# MegaButton_Shiled.net
KiCad netlist of a schematic drawn in EAGLE
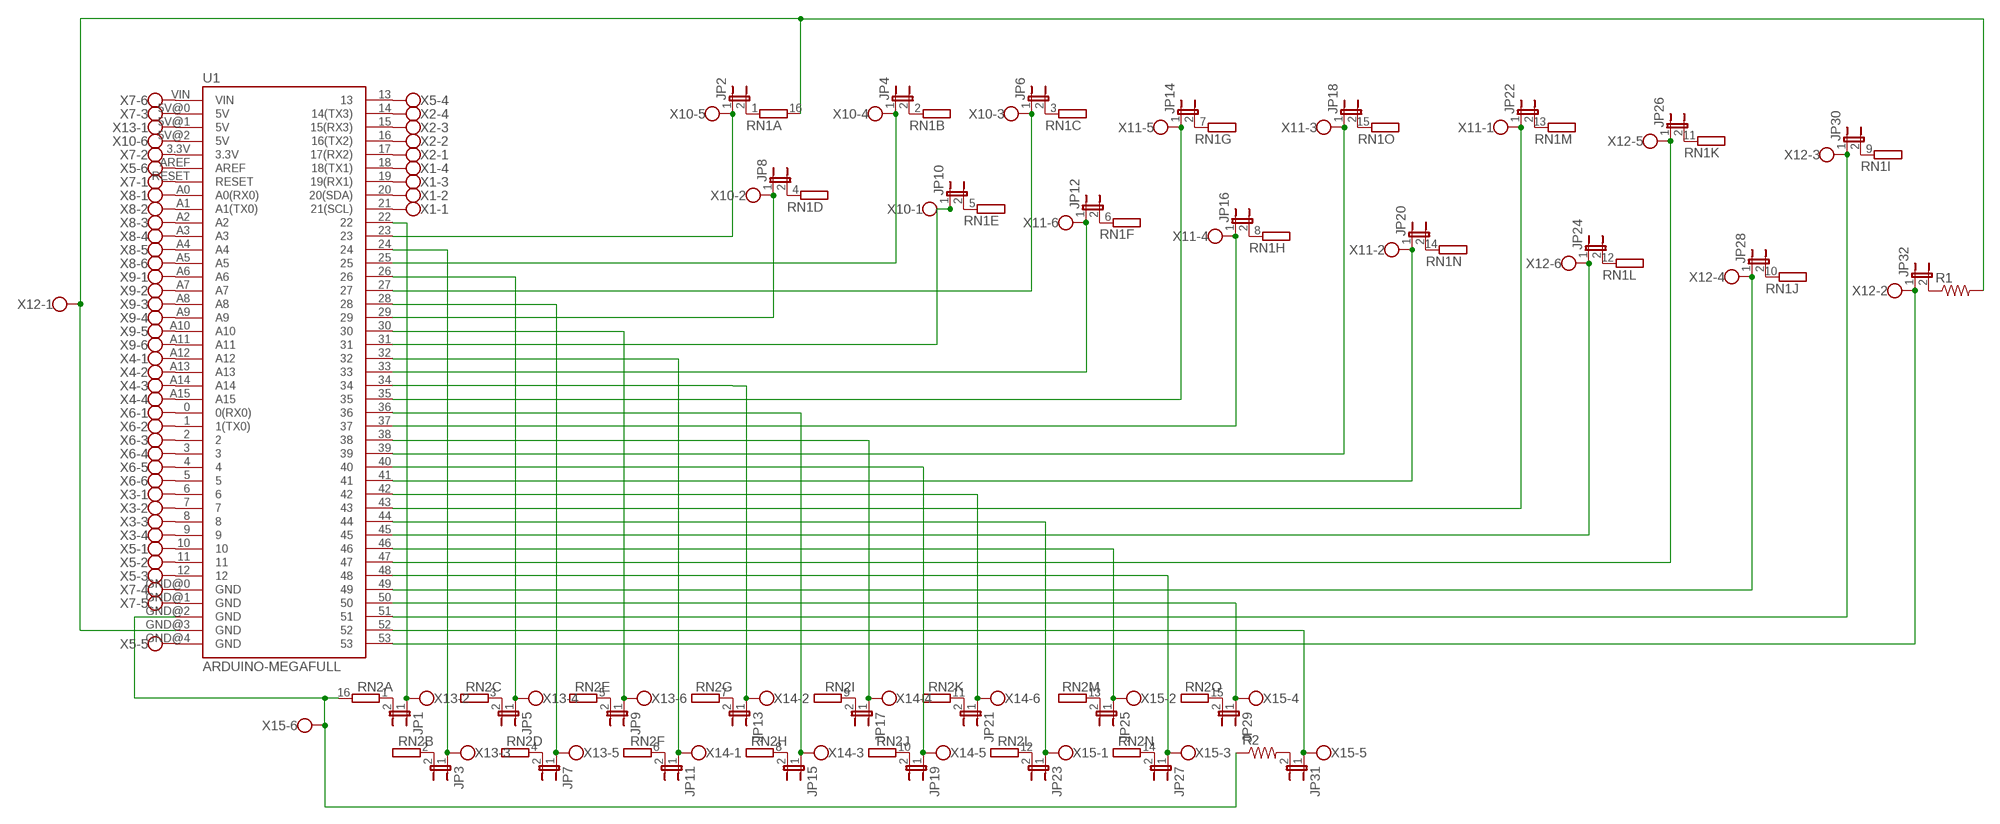
[diagram p0: schematic, sheet 1, part 1 of 2]
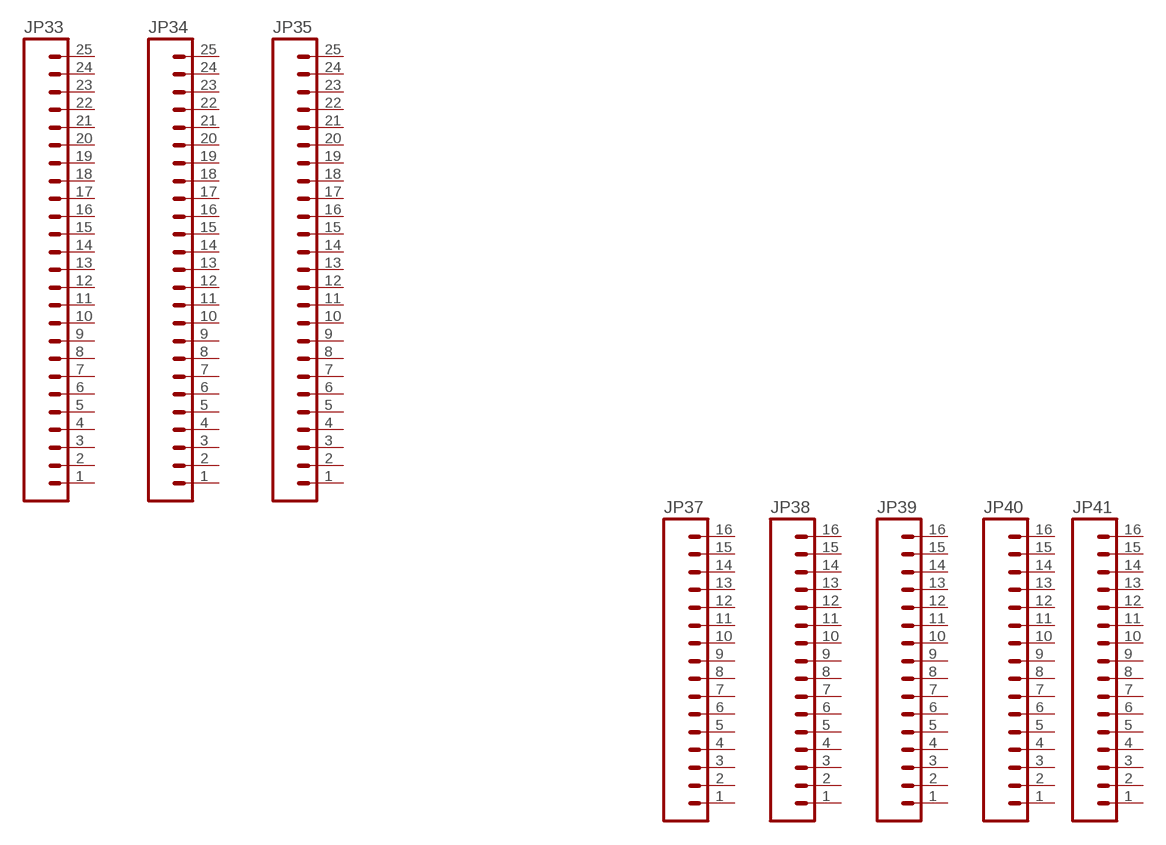
[diagram p1: schematic, sheet 1, part 2 of 2]

(export (version "E")
  (design (tool "Eeschema 10.0.6"))
  (components
    (comp (ref "JP1")
      (value "JP1E")
      (footprint "eagle-import:JP1")
      (libsource (lib "eagle-import") (part "JP1E"))
    )
    (comp (ref "JP2")
      (value "JP1E")
      (footprint "eagle-import:JP1")
      (libsource (lib "eagle-import") (part "JP1E"))
    )
    (comp (ref "JP3")
      (value "JP1E")
      (footprint "eagle-import:JP1")
      (libsource (lib "eagle-import") (part "JP1E"))
    )
    (comp (ref "JP4")
      (value "JP1E")
      (footprint "eagle-import:JP1")
      (libsource (lib "eagle-import") (part "JP1E"))
    )
    (comp (ref "JP5")
      (value "JP1E")
      (footprint "eagle-import:JP1")
      (libsource (lib "eagle-import") (part "JP1E"))
    )
    (comp (ref "JP6")
      (value "JP1E")
      (footprint "eagle-import:JP1")
      (libsource (lib "eagle-import") (part "JP1E"))
    )
    (comp (ref "JP7")
      (value "JP1E")
      (footprint "eagle-import:JP1")
      (libsource (lib "eagle-import") (part "JP1E"))
    )
    (comp (ref "JP8")
      (value "JP1E")
      (footprint "eagle-import:JP1")
      (libsource (lib "eagle-import") (part "JP1E"))
    )
    (comp (ref "JP9")
      (value "JP1E")
      (footprint "eagle-import:JP1")
      (libsource (lib "eagle-import") (part "JP1E"))
    )
    (comp (ref "JP10")
      (value "JP1E")
      (footprint "eagle-import:JP1")
      (libsource (lib "eagle-import") (part "JP1E"))
    )
    (comp (ref "JP11")
      (value "JP1E")
      (footprint "eagle-import:JP1")
      (libsource (lib "eagle-import") (part "JP1E"))
    )
    (comp (ref "JP12")
      (value "JP1E")
      (footprint "eagle-import:JP1")
      (libsource (lib "eagle-import") (part "JP1E"))
    )
    (comp (ref "JP13")
      (value "JP1E")
      (footprint "eagle-import:JP1")
      (libsource (lib "eagle-import") (part "JP1E"))
    )
    (comp (ref "JP14")
      (value "JP1E")
      (footprint "eagle-import:JP1")
      (libsource (lib "eagle-import") (part "JP1E"))
    )
    (comp (ref "JP15")
      (value "JP1E")
      (footprint "eagle-import:JP1")
      (libsource (lib "eagle-import") (part "JP1E"))
    )
    (comp (ref "JP16")
      (value "JP1E")
      (footprint "eagle-import:JP1")
      (libsource (lib "eagle-import") (part "JP1E"))
    )
    (comp (ref "JP17")
      (value "JP1E")
      (footprint "eagle-import:JP1")
      (libsource (lib "eagle-import") (part "JP1E"))
    )
    (comp (ref "JP18")
      (value "JP1E")
      (footprint "eagle-import:JP1")
      (libsource (lib "eagle-import") (part "JP1E"))
    )
    (comp (ref "JP19")
      (value "JP1E")
      (footprint "eagle-import:JP1")
      (libsource (lib "eagle-import") (part "JP1E"))
    )
    (comp (ref "JP20")
      (value "JP1E")
      (footprint "eagle-import:JP1")
      (libsource (lib "eagle-import") (part "JP1E"))
    )
    (comp (ref "JP21")
      (value "JP1E")
      (footprint "eagle-import:JP1")
      (libsource (lib "eagle-import") (part "JP1E"))
    )
    (comp (ref "JP22")
      (value "JP1E")
      (footprint "eagle-import:JP1")
      (libsource (lib "eagle-import") (part "JP1E"))
    )
    (comp (ref "JP23")
      (value "JP1E")
      (footprint "eagle-import:JP1")
      (libsource (lib "eagle-import") (part "JP1E"))
    )
    (comp (ref "JP24")
      (value "JP1E")
      (footprint "eagle-import:JP1")
      (libsource (lib "eagle-import") (part "JP1E"))
    )
    (comp (ref "JP25")
      (value "JP1E")
      (footprint "eagle-import:JP1")
      (libsource (lib "eagle-import") (part "JP1E"))
    )
    (comp (ref "JP26")
      (value "JP1E")
      (footprint "eagle-import:JP1")
      (libsource (lib "eagle-import") (part "JP1E"))
    )
    (comp (ref "JP27")
      (value "JP1E")
      (footprint "eagle-import:JP1")
      (libsource (lib "eagle-import") (part "JP1E"))
    )
    (comp (ref "JP28")
      (value "JP1E")
      (footprint "eagle-import:JP1")
      (libsource (lib "eagle-import") (part "JP1E"))
    )
    (comp (ref "JP29")
      (value "JP1E")
      (footprint "eagle-import:JP1")
      (libsource (lib "eagle-import") (part "JP1E"))
    )
    (comp (ref "JP30")
      (value "JP1E")
      (footprint "eagle-import:JP1")
      (libsource (lib "eagle-import") (part "JP1E"))
    )
    (comp (ref "JP31")
      (value "JP1E")
      (footprint "eagle-import:JP1")
      (libsource (lib "eagle-import") (part "JP1E"))
    )
    (comp (ref "JP32")
      (value "JP1E")
      (footprint "eagle-import:JP1")
      (libsource (lib "eagle-import") (part "JP1E"))
    )
    (comp (ref "JP33")
      (value "M25PTH")
      (footprint "eagle-import:1X25")
      (libsource (lib "eagle-import") (part "M25PTH"))
    )
    (comp (ref "JP34")
      (value "M25PTH")
      (footprint "eagle-import:1X25")
      (libsource (lib "eagle-import") (part "M25PTH"))
    )
    (comp (ref "JP35")
      (value "M25PTH")
      (footprint "eagle-import:1X25")
      (libsource (lib "eagle-import") (part "M25PTH"))
    )
    (comp (ref "JP37")
      (value "M16PTH")
      (footprint "eagle-import:1X16")
      (libsource (lib "eagle-import") (part "M16PTH"))
    )
    (comp (ref "JP38")
      (value "M16PTH")
      (footprint "eagle-import:1X16")
      (libsource (lib "eagle-import") (part "M16PTH"))
    )
    (comp (ref "JP39")
      (value "M16PTH")
      (footprint "eagle-import:1X16")
      (libsource (lib "eagle-import") (part "M16PTH"))
    )
    (comp (ref "JP40")
      (value "M16PTH")
      (footprint "eagle-import:1X16")
      (libsource (lib "eagle-import") (part "M16PTH"))
    )
    (comp (ref "JP41")
      (value "M16PTH")
      (footprint "eagle-import:1X16")
      (libsource (lib "eagle-import") (part "M16PTH"))
    )
    (comp (ref "R1")
      (value "R-US_0204/5")
      (footprint "eagle-import:0204_5")
      (libsource (lib "eagle-import") (part "R-US_0204/5"))
    )
    (comp (ref "R2")
      (value "R-US_0204/5")
      (footprint "eagle-import:0204_5")
      (libsource (lib "eagle-import") (part "R-US_0204/5"))
    )
    (comp (ref "RN1")
      (value "E15R")
      (footprint "eagle-import:DIL16")
      (libsource (lib "eagle-import") (part "E15R"))
    )
    (comp (ref "RN2")
      (value "E15R")
      (footprint "eagle-import:DIL16")
      (libsource (lib "eagle-import") (part "E15R"))
    )
    (comp (ref "U1")
      (value "ARDUINO-MEGAFULL")
      (footprint "eagle-import:ARDUINO_MEGA")
      (libsource (lib "eagle-import") (part "ARDUINO-MEGAFULL"))
    )
    (comp (ref "X1")
      (value "W237-4")
      (footprint "eagle-import:W237-4")
      (libsource (lib "eagle-import") (part "W237-4"))
    )
    (comp (ref "X2")
      (value "W237-4")
      (footprint "eagle-import:W237-4")
      (libsource (lib "eagle-import") (part "W237-4"))
    )
    (comp (ref "X3")
      (value "W237-4")
      (footprint "eagle-import:W237-4")
      (libsource (lib "eagle-import") (part "W237-4"))
    )
    (comp (ref "X4")
      (value "W237-4")
      (footprint "eagle-import:W237-4")
      (libsource (lib "eagle-import") (part "W237-4"))
    )
    (comp (ref "X5")
      (value "W237-136")
      (footprint "eagle-import:W237-136")
      (fields (field (name "MPN") "237-136"))
      (libsource (lib "eagle-import") (part "W237-136"))
    )
    (comp (ref "X6")
      (value "W237-136")
      (footprint "eagle-import:W237-136")
      (fields (field (name "MPN") "237-136"))
      (libsource (lib "eagle-import") (part "W237-136"))
    )
    (comp (ref "X7")
      (value "W237-136")
      (footprint "eagle-import:W237-136")
      (fields (field (name "MPN") "237-136"))
      (libsource (lib "eagle-import") (part "W237-136"))
    )
    (comp (ref "X8")
      (value "W237-6")
      (footprint "eagle-import:W237-6")
      (libsource (lib "eagle-import") (part "W237-6"))
    )
    (comp (ref "X9")
      (value "W237-6")
      (footprint "eagle-import:W237-6")
      (libsource (lib "eagle-import") (part "W237-6"))
    )
    (comp (ref "X10")
      (value "W237-6")
      (footprint "eagle-import:W237-6")
      (libsource (lib "eagle-import") (part "W237-6"))
    )
    (comp (ref "X11")
      (value "W237-6")
      (footprint "eagle-import:W237-6")
      (libsource (lib "eagle-import") (part "W237-6"))
    )
    (comp (ref "X12")
      (value "W237-6")
      (footprint "eagle-import:W237-6")
      (libsource (lib "eagle-import") (part "W237-6"))
    )
    (comp (ref "X13")
      (value "W237-6")
      (footprint "eagle-import:W237-6")
      (libsource (lib "eagle-import") (part "W237-6"))
    )
    (comp (ref "X14")
      (value "W237-6")
      (footprint "eagle-import:W237-6")
      (libsource (lib "eagle-import") (part "W237-6"))
    )
    (comp (ref "X15")
      (value "W237-6")
      (footprint "eagle-import:W237-6")
      (libsource (lib "eagle-import") (part "W237-6"))
    )
  )
  (nets
    (net (code "1") (name "Net-(JP1-Pad2)") (class "Default")
      (node (ref "JP1") (pin "2") (pinfunction "2_2") (pintype "passive"))
      (node (ref "RN2") (pin "1") (pinfunction "1_1") (pintype "passive"))
    )
    (net (code "2") (name "Net-(JP2-Pad2)") (class "Default")
      (node (ref "JP2") (pin "2") (pinfunction "2_2") (pintype "passive"))
      (node (ref "RN1") (pin "1") (pinfunction "1_1") (pintype "passive"))
    )
    (net (code "3") (name "Net-(JP31-Pad2)") (class "Default")
      (node (ref "JP31") (pin "2") (pinfunction "2_2") (pintype "passive"))
      (node (ref "R2") (pin "2") (pinfunction "2_2") (pintype "passive"))
    )
    (net (code "4") (name "Net-(JP32-Pad2)") (class "Default")
      (node (ref "JP32") (pin "2") (pinfunction "2_2") (pintype "passive"))
      (node (ref "R1") (pin "1") (pinfunction "1_1") (pintype "passive"))
    )
    (net (code "5") (name "Net-(RN1A-2)") (class "Default")
      (node (ref "R1") (pin "2") (pinfunction "2_2") (pintype "passive"))
      (node (ref "RN1") (pin "16") (pinfunction "2_16") (pintype "passive"))
      (node (ref "U1") (pin "GND@3") (pinfunction "GND_GND@3") (pintype "bidirectional"))
      (node (ref "X12") (pin "1") (pinfunction "KL_1") (pintype "passive"))
    )
    (net (code "6") (name "Net-(RN1B-1)") (class "Default")
      (node (ref "JP4") (pin "2") (pinfunction "2_2") (pintype "passive"))
      (node (ref "RN1") (pin "2") (pinfunction "1_2") (pintype "passive"))
    )
    (net (code "7") (name "Net-(RN1C-1)") (class "Default")
      (node (ref "JP6") (pin "2") (pinfunction "2_2") (pintype "passive"))
      (node (ref "RN1") (pin "3") (pinfunction "1_3") (pintype "passive"))
    )
    (net (code "8") (name "Net-(RN1D-1)") (class "Default")
      (node (ref "JP8") (pin "2") (pinfunction "2_2") (pintype "passive"))
      (node (ref "RN1") (pin "4") (pinfunction "1_4") (pintype "passive"))
    )
    (net (code "9") (name "Net-(RN1E-1)") (class "Default")
      (node (ref "JP10") (pin "2") (pinfunction "2_2") (pintype "passive"))
      (node (ref "RN1") (pin "5") (pinfunction "1_5") (pintype "passive"))
    )
    (net (code "10") (name "Net-(RN1F-1)") (class "Default")
      (node (ref "JP12") (pin "2") (pinfunction "2_2") (pintype "passive"))
      (node (ref "RN1") (pin "6") (pinfunction "1_6") (pintype "passive"))
    )
    (net (code "11") (name "Net-(RN1G-1)") (class "Default")
      (node (ref "JP14") (pin "2") (pinfunction "2_2") (pintype "passive"))
      (node (ref "RN1") (pin "7") (pinfunction "1_7") (pintype "passive"))
    )
    (net (code "12") (name "Net-(RN1H-1)") (class "Default")
      (node (ref "JP16") (pin "2") (pinfunction "2_2") (pintype "passive"))
      (node (ref "RN1") (pin "8") (pinfunction "1_8") (pintype "passive"))
    )
    (net (code "13") (name "Net-(RN1I-1)") (class "Default")
      (node (ref "JP30") (pin "2") (pinfunction "2_2") (pintype "passive"))
      (node (ref "RN1") (pin "9") (pinfunction "1_9") (pintype "passive"))
    )
    (net (code "14") (name "Net-(RN1J-1)") (class "Default")
      (node (ref "JP28") (pin "2") (pinfunction "2_2") (pintype "passive"))
      (node (ref "RN1") (pin "10") (pinfunction "1_10") (pintype "passive"))
    )
    (net (code "15") (name "Net-(RN1K-1)") (class "Default")
      (node (ref "JP26") (pin "2") (pinfunction "2_2") (pintype "passive"))
      (node (ref "RN1") (pin "11") (pinfunction "1_11") (pintype "passive"))
    )
    (net (code "16") (name "Net-(RN1L-1)") (class "Default")
      (node (ref "JP24") (pin "2") (pinfunction "2_2") (pintype "passive"))
      (node (ref "RN1") (pin "12") (pinfunction "1_12") (pintype "passive"))
    )
    (net (code "17") (name "Net-(RN1M-1)") (class "Default")
      (node (ref "JP22") (pin "2") (pinfunction "2_2") (pintype "passive"))
      (node (ref "RN1") (pin "13") (pinfunction "1_13") (pintype "passive"))
    )
    (net (code "18") (name "Net-(RN1N-1)") (class "Default")
      (node (ref "JP20") (pin "2") (pinfunction "2_2") (pintype "passive"))
      (node (ref "RN1") (pin "14") (pinfunction "1_14") (pintype "passive"))
    )
    (net (code "19") (name "Net-(RN1O-1)") (class "Default")
      (node (ref "JP18") (pin "2") (pinfunction "2_2") (pintype "passive"))
      (node (ref "RN1") (pin "15") (pinfunction "1_15") (pintype "passive"))
    )
    (net (code "20") (name "Net-(RN2A-2)") (class "Default")
      (node (ref "R2") (pin "1") (pinfunction "1_1") (pintype "passive"))
      (node (ref "RN2") (pin "16") (pinfunction "2_16") (pintype "passive"))
      (node (ref "U1") (pin "GND@2") (pinfunction "GND_GND@2") (pintype "bidirectional"))
      (node (ref "X15") (pin "6") (pinfunction "KL_6") (pintype "passive"))
    )
    (net (code "21") (name "Net-(RN2B-1)") (class "Default")
      (node (ref "JP3") (pin "2") (pinfunction "2_2") (pintype "passive"))
      (node (ref "RN2") (pin "2") (pinfunction "1_2") (pintype "passive"))
    )
    (net (code "22") (name "Net-(RN2C-1)") (class "Default")
      (node (ref "JP5") (pin "2") (pinfunction "2_2") (pintype "passive"))
      (node (ref "RN2") (pin "3") (pinfunction "1_3") (pintype "passive"))
    )
    (net (code "23") (name "Net-(RN2D-1)") (class "Default")
      (node (ref "JP7") (pin "2") (pinfunction "2_2") (pintype "passive"))
      (node (ref "RN2") (pin "4") (pinfunction "1_4") (pintype "passive"))
    )
    (net (code "24") (name "Net-(RN2E-1)") (class "Default")
      (node (ref "JP9") (pin "2") (pinfunction "2_2") (pintype "passive"))
      (node (ref "RN2") (pin "5") (pinfunction "1_5") (pintype "passive"))
    )
    (net (code "25") (name "Net-(RN2F-1)") (class "Default")
      (node (ref "JP11") (pin "2") (pinfunction "2_2") (pintype "passive"))
      (node (ref "RN2") (pin "6") (pinfunction "1_6") (pintype "passive"))
    )
    (net (code "26") (name "Net-(RN2G-1)") (class "Default")
      (node (ref "JP13") (pin "2") (pinfunction "2_2") (pintype "passive"))
      (node (ref "RN2") (pin "7") (pinfunction "1_7") (pintype "passive"))
    )
    (net (code "27") (name "Net-(RN2H-1)") (class "Default")
      (node (ref "JP15") (pin "2") (pinfunction "2_2") (pintype "passive"))
      (node (ref "RN2") (pin "8") (pinfunction "1_8") (pintype "passive"))
    )
    (net (code "28") (name "Net-(RN2I-1)") (class "Default")
      (node (ref "JP17") (pin "2") (pinfunction "2_2") (pintype "passive"))
      (node (ref "RN2") (pin "9") (pinfunction "1_9") (pintype "passive"))
    )
    (net (code "29") (name "Net-(RN2J-1)") (class "Default")
      (node (ref "JP19") (pin "2") (pinfunction "2_2") (pintype "passive"))
      (node (ref "RN2") (pin "10") (pinfunction "1_10") (pintype "passive"))
    )
    (net (code "30") (name "Net-(RN2K-1)") (class "Default")
      (node (ref "JP21") (pin "2") (pinfunction "2_2") (pintype "passive"))
      (node (ref "RN2") (pin "11") (pinfunction "1_11") (pintype "passive"))
    )
    (net (code "31") (name "Net-(RN2L-1)") (class "Default")
      (node (ref "JP23") (pin "2") (pinfunction "2_2") (pintype "passive"))
      (node (ref "RN2") (pin "12") (pinfunction "1_12") (pintype "passive"))
    )
    (net (code "32") (name "Net-(RN2M-1)") (class "Default")
      (node (ref "JP25") (pin "2") (pinfunction "2_2") (pintype "passive"))
      (node (ref "RN2") (pin "13") (pinfunction "1_13") (pintype "passive"))
    )
    (net (code "33") (name "Net-(RN2N-1)") (class "Default")
      (node (ref "JP27") (pin "2") (pinfunction "2_2") (pintype "passive"))
      (node (ref "RN2") (pin "14") (pinfunction "1_14") (pintype "passive"))
    )
    (net (code "34") (name "Net-(RN2O-1)") (class "Default")
      (node (ref "JP29") (pin "2") (pinfunction "2_2") (pintype "passive"))
      (node (ref "RN2") (pin "15") (pinfunction "1_15") (pintype "passive"))
    )
    (net (code "35") (name "Net-(U1-0(RX0))") (class "Default")
      (node (ref "U1") (pin "0") (pinfunction "0(RX0)_0") (pintype "bidirectional"))
      (node (ref "X6") (pin "1") (pinfunction "KL_1") (pintype "passive"))
    )
    (net (code "36") (name "Net-(U1-1(TX0))") (class "Default")
      (node (ref "U1") (pin "1") (pinfunction "1(TX0)_1") (pintype "bidirectional"))
      (node (ref "X6") (pin "2") (pinfunction "KL_2") (pintype "passive"))
    )
    (net (code "37") (name "Net-(U1-14(TX3))") (class "Default")
      (node (ref "U1") (pin "14") (pinfunction "14(TX3)_14") (pintype "bidirectional"))
      (node (ref "X2") (pin "4") (pinfunction "KL_4") (pintype "passive"))
    )
    (net (code "38") (name "Net-(U1-15(RX3))") (class "Default")
      (node (ref "U1") (pin "15") (pinfunction "15(RX3)_15") (pintype "bidirectional"))
      (node (ref "X2") (pin "3") (pinfunction "KL_3") (pintype "passive"))
    )
    (net (code "39") (name "Net-(U1-16(TX2))") (class "Default")
      (node (ref "U1") (pin "16") (pinfunction "16(TX2)_16") (pintype "bidirectional"))
      (node (ref "X2") (pin "2") (pinfunction "KL_2") (pintype "passive"))
    )
    (net (code "40") (name "Net-(U1-17(RX2))") (class "Default")
      (node (ref "U1") (pin "17") (pinfunction "17(RX2)_17") (pintype "bidirectional"))
      (node (ref "X2") (pin "1") (pinfunction "KL_1") (pintype "passive"))
    )
    (net (code "41") (name "Net-(U1-18(TX1))") (class "Default")
      (node (ref "U1") (pin "18") (pinfunction "18(TX1)_18") (pintype "bidirectional"))
      (node (ref "X1") (pin "4") (pinfunction "KL_4") (pintype "passive"))
    )
    (net (code "42") (name "Net-(U1-19(RX1))") (class "Default")
      (node (ref "U1") (pin "19") (pinfunction "19(RX1)_19") (pintype "bidirectional"))
      (node (ref "X1") (pin "3") (pinfunction "KL_3") (pintype "passive"))
    )
    (net (code "43") (name "Net-(U1-20(SDA))") (class "Default")
      (node (ref "U1") (pin "20") (pinfunction "20(SDA)_20") (pintype "bidirectional"))
      (node (ref "X1") (pin "2") (pinfunction "KL_2") (pintype "passive"))
    )
    (net (code "44") (name "Net-(U1-21(SCL))") (class "Default")
      (node (ref "U1") (pin "21") (pinfunction "21(SCL)_21") (pintype "bidirectional"))
      (node (ref "X1") (pin "1") (pinfunction "KL_1") (pintype "passive"))
    )
    (net (code "45") (name "Net-(U1-A0(RX0))") (class "Default")
      (node (ref "U1") (pin "A0") (pinfunction "A0(RX0)_A0") (pintype "bidirectional"))
      (node (ref "X8") (pin "1") (pinfunction "KL_1") (pintype "passive"))
    )
    (net (code "46") (name "Net-(U1-A1(TX0))") (class "Default")
      (node (ref "U1") (pin "A1") (pinfunction "A1(TX0)_A1") (pintype "bidirectional"))
      (node (ref "X8") (pin "2") (pinfunction "KL_2") (pintype "passive"))
    )
    (net (code "47") (name "Net-(X3A-KL)") (class "Default")
      (node (ref "U1") (pin "6") (pinfunction "6_6") (pintype "bidirectional"))
      (node (ref "X3") (pin "1") (pinfunction "KL_1") (pintype "passive"))
    )
    (net (code "48") (name "Net-(X3B-KL)") (class "Default")
      (node (ref "U1") (pin "7") (pinfunction "7_7") (pintype "bidirectional"))
      (node (ref "X3") (pin "2") (pinfunction "KL_2") (pintype "passive"))
    )
    (net (code "49") (name "Net-(X3C-KL)") (class "Default")
      (node (ref "U1") (pin "8") (pinfunction "8_8") (pintype "bidirectional"))
      (node (ref "X3") (pin "3") (pinfunction "KL_3") (pintype "passive"))
    )
    (net (code "50") (name "Net-(X3D-KL)") (class "Default")
      (node (ref "U1") (pin "9") (pinfunction "9_9") (pintype "bidirectional"))
      (node (ref "X3") (pin "4") (pinfunction "KL_4") (pintype "passive"))
    )
    (net (code "51") (name "Net-(X4A-KL)") (class "Default")
      (node (ref "U1") (pin "A12") (pinfunction "A12_A12") (pintype "bidirectional"))
      (node (ref "X4") (pin "1") (pinfunction "KL_1") (pintype "passive"))
    )
    (net (code "52") (name "Net-(X4B-KL)") (class "Default")
      (node (ref "U1") (pin "A13") (pinfunction "A13_A13") (pintype "bidirectional"))
      (node (ref "X4") (pin "2") (pinfunction "KL_2") (pintype "passive"))
    )
    (net (code "53") (name "Net-(X4C-KL)") (class "Default")
      (node (ref "U1") (pin "A14") (pinfunction "A14_A14") (pintype "bidirectional"))
      (node (ref "X4") (pin "3") (pinfunction "KL_3") (pintype "passive"))
    )
    (net (code "54") (name "Net-(X4D-KL)") (class "Default")
      (node (ref "U1") (pin "A15") (pinfunction "A15_A15") (pintype "bidirectional"))
      (node (ref "X4") (pin "4") (pinfunction "KL_4") (pintype "passive"))
    )
    (net (code "55") (name "Net-(X5A-KL)") (class "Default")
      (node (ref "U1") (pin "10") (pinfunction "10_10") (pintype "bidirectional"))
      (node (ref "X5") (pin "1") (pinfunction "KL_1") (pintype "passive"))
    )
    (net (code "56") (name "Net-(X5B-KL)") (class "Default")
      (node (ref "U1") (pin "11") (pinfunction "11_11") (pintype "bidirectional"))
      (node (ref "X5") (pin "2") (pinfunction "KL_2") (pintype "passive"))
    )
    (net (code "57") (name "Net-(X5C-KL)") (class "Default")
      (node (ref "U1") (pin "12") (pinfunction "12_12") (pintype "bidirectional"))
      (node (ref "X5") (pin "3") (pinfunction "KL_3") (pintype "passive"))
    )
    (net (code "58") (name "Net-(X5D-KL)") (class "Default")
      (node (ref "U1") (pin "13") (pinfunction "13_13") (pintype "bidirectional"))
      (node (ref "X5") (pin "4") (pinfunction "KL_4") (pintype "passive"))
    )
    (net (code "59") (name "Net-(X5E-KL)") (class "Default")
      (node (ref "U1") (pin "GND@4") (pinfunction "GND_GND@4") (pintype "bidirectional"))
      (node (ref "X5") (pin "5") (pinfunction "KL_5") (pintype "passive"))
    )
    (net (code "60") (name "Net-(X5F-KL)") (class "Default")
      (node (ref "U1") (pin "AREF") (pinfunction "AREF_AREF") (pintype "bidirectional"))
      (node (ref "X5") (pin "6") (pinfunction "KL_6") (pintype "passive"))
    )
    (net (code "61") (name "Net-(X6C-KL)") (class "Default")
      (node (ref "U1") (pin "2") (pinfunction "2_2") (pintype "bidirectional"))
      (node (ref "X6") (pin "3") (pinfunction "KL_3") (pintype "passive"))
    )
    (net (code "62") (name "Net-(X6D-KL)") (class "Default")
      (node (ref "U1") (pin "3") (pinfunction "3_3") (pintype "bidirectional"))
      (node (ref "X6") (pin "4") (pinfunction "KL_4") (pintype "passive"))
    )
    (net (code "63") (name "Net-(X6E-KL)") (class "Default")
      (node (ref "U1") (pin "4") (pinfunction "4_4") (pintype "bidirectional"))
      (node (ref "X6") (pin "5") (pinfunction "KL_5") (pintype "passive"))
    )
    (net (code "64") (name "Net-(X6F-KL)") (class "Default")
      (node (ref "U1") (pin "5") (pinfunction "5_5") (pintype "bidirectional"))
      (node (ref "X6") (pin "6") (pinfunction "KL_6") (pintype "passive"))
    )
    (net (code "65") (name "Net-(X7A-KL)") (class "Default")
      (node (ref "U1") (pin "RESET") (pinfunction "RESET_RESET") (pintype "bidirectional"))
      (node (ref "X7") (pin "1") (pinfunction "KL_1") (pintype "passive"))
    )
    (net (code "66") (name "Net-(X7B-KL)") (class "Default")
      (node (ref "U1") (pin "3.3V") (pinfunction "3.3V_3.3V") (pintype "bidirectional"))
      (node (ref "X7") (pin "2") (pinfunction "KL_2") (pintype "passive"))
    )
    (net (code "67") (name "Net-(X7C-KL)") (class "Default")
      (node (ref "U1") (pin "5V@0") (pinfunction "5V_5V@0") (pintype "bidirectional"))
      (node (ref "X7") (pin "3") (pinfunction "KL_3") (pintype "passive"))
    )
    (net (code "68") (name "Net-(X7D-KL)") (class "Default")
      (node (ref "U1") (pin "GND@0") (pinfunction "GND_GND@0") (pintype "bidirectional"))
      (node (ref "X7") (pin "4") (pinfunction "KL_4") (pintype "passive"))
    )
    (net (code "69") (name "Net-(X7E-KL)") (class "Default")
      (node (ref "U1") (pin "GND@1") (pinfunction "GND_GND@1") (pintype "bidirectional"))
      (node (ref "X7") (pin "5") (pinfunction "KL_5") (pintype "passive"))
    )
    (net (code "70") (name "Net-(X7F-KL)") (class "Default")
      (node (ref "U1") (pin "VIN") (pinfunction "VIN_VIN") (pintype "bidirectional"))
      (node (ref "X7") (pin "6") (pinfunction "KL_6") (pintype "passive"))
    )
    (net (code "71") (name "Net-(X8C-KL)") (class "Default")
      (node (ref "U1") (pin "A2") (pinfunction "A2_A2") (pintype "bidirectional"))
      (node (ref "X8") (pin "3") (pinfunction "KL_3") (pintype "passive"))
    )
    (net (code "72") (name "Net-(X8D-KL)") (class "Default")
      (node (ref "U1") (pin "A3") (pinfunction "A3_A3") (pintype "bidirectional"))
      (node (ref "X8") (pin "4") (pinfunction "KL_4") (pintype "passive"))
    )
    (net (code "73") (name "Net-(X8E-KL)") (class "Default")
      (node (ref "U1") (pin "A4") (pinfunction "A4_A4") (pintype "bidirectional"))
      (node (ref "X8") (pin "5") (pinfunction "KL_5") (pintype "passive"))
    )
    (net (code "74") (name "Net-(X8F-KL)") (class "Default")
      (node (ref "U1") (pin "A5") (pinfunction "A5_A5") (pintype "bidirectional"))
      (node (ref "X8") (pin "6") (pinfunction "KL_6") (pintype "passive"))
    )
    (net (code "75") (name "Net-(X9A-KL)") (class "Default")
      (node (ref "U1") (pin "A6") (pinfunction "A6_A6") (pintype "bidirectional"))
      (node (ref "X9") (pin "1") (pinfunction "KL_1") (pintype "passive"))
    )
    (net (code "76") (name "Net-(X9B-KL)") (class "Default")
      (node (ref "U1") (pin "A7") (pinfunction "A7_A7") (pintype "bidirectional"))
      (node (ref "X9") (pin "2") (pinfunction "KL_2") (pintype "passive"))
    )
    (net (code "77") (name "Net-(X9C-KL)") (class "Default")
      (node (ref "U1") (pin "A8") (pinfunction "A8_A8") (pintype "bidirectional"))
      (node (ref "X9") (pin "3") (pinfunction "KL_3") (pintype "passive"))
    )
    (net (code "78") (name "Net-(X9D-KL)") (class "Default")
      (node (ref "U1") (pin "A9") (pinfunction "A9_A9") (pintype "bidirectional"))
      (node (ref "X9") (pin "4") (pinfunction "KL_4") (pintype "passive"))
    )
    (net (code "79") (name "Net-(X9E-KL)") (class "Default")
      (node (ref "U1") (pin "A10") (pinfunction "A10_A10") (pintype "bidirectional"))
      (node (ref "X9") (pin "5") (pinfunction "KL_5") (pintype "passive"))
    )
    (net (code "80") (name "Net-(X9F-KL)") (class "Default")
      (node (ref "U1") (pin "A11") (pinfunction "A11_A11") (pintype "bidirectional"))
      (node (ref "X9") (pin "6") (pinfunction "KL_6") (pintype "passive"))
    )
    (net (code "81") (name "Net-(X10A-KL)") (class "Default")
      (node (ref "JP10") (pin "1") (pinfunction "1_1") (pintype "passive"))
      (node (ref "U1") (pin "31") (pinfunction "31_31") (pintype "bidirectional"))
      (node (ref "X10") (pin "1") (pinfunction "KL_1") (pintype "passive"))
    )
    (net (code "82") (name "Net-(X10B-KL)") (class "Default")
      (node (ref "JP8") (pin "1") (pinfunction "1_1") (pintype "passive"))
      (node (ref "U1") (pin "29") (pinfunction "29_29") (pintype "bidirectional"))
      (node (ref "X10") (pin "2") (pinfunction "KL_2") (pintype "passive"))
    )
    (net (code "83") (name "Net-(X10C-KL)") (class "Default")
      (node (ref "JP6") (pin "1") (pinfunction "1_1") (pintype "passive"))
      (node (ref "U1") (pin "27") (pinfunction "27_27") (pintype "bidirectional"))
      (node (ref "X10") (pin "3") (pinfunction "KL_3") (pintype "passive"))
    )
    (net (code "84") (name "Net-(X10D-KL)") (class "Default")
      (node (ref "JP4") (pin "1") (pinfunction "1_1") (pintype "passive"))
      (node (ref "U1") (pin "25") (pinfunction "25_25") (pintype "bidirectional"))
      (node (ref "X10") (pin "4") (pinfunction "KL_4") (pintype "passive"))
    )
    (net (code "85") (name "Net-(X10E-KL)") (class "Default")
      (node (ref "JP2") (pin "1") (pinfunction "1_1") (pintype "passive"))
      (node (ref "U1") (pin "23") (pinfunction "23_23") (pintype "bidirectional"))
      (node (ref "X10") (pin "5") (pinfunction "KL_5") (pintype "passive"))
    )
    (net (code "86") (name "Net-(X10F-KL)") (class "Default")
      (node (ref "U1") (pin "5V@2") (pinfunction "5V_5V@2") (pintype "bidirectional"))
      (node (ref "X10") (pin "6") (pinfunction "KL_6") (pintype "passive"))
    )
    (net (code "87") (name "Net-(X11A-KL)") (class "Default")
      (node (ref "JP22") (pin "1") (pinfunction "1_1") (pintype "passive"))
      (node (ref "U1") (pin "43") (pinfunction "43_43") (pintype "bidirectional"))
      (node (ref "X11") (pin "1") (pinfunction "KL_1") (pintype "passive"))
    )
    (net (code "88") (name "Net-(X11B-KL)") (class "Default")
      (node (ref "JP20") (pin "1") (pinfunction "1_1") (pintype "passive"))
      (node (ref "U1") (pin "41") (pinfunction "41_41") (pintype "bidirectional"))
      (node (ref "X11") (pin "2") (pinfunction "KL_2") (pintype "passive"))
    )
    (net (code "89") (name "Net-(X11C-KL)") (class "Default")
      (node (ref "JP18") (pin "1") (pinfunction "1_1") (pintype "passive"))
      (node (ref "U1") (pin "39") (pinfunction "39_39") (pintype "bidirectional"))
      (node (ref "X11") (pin "3") (pinfunction "KL_3") (pintype "passive"))
    )
    (net (code "90") (name "Net-(X11D-KL)") (class "Default")
      (node (ref "JP16") (pin "1") (pinfunction "1_1") (pintype "passive"))
      (node (ref "U1") (pin "37") (pinfunction "37_37") (pintype "bidirectional"))
      (node (ref "X11") (pin "4") (pinfunction "KL_4") (pintype "passive"))
    )
    (net (code "91") (name "Net-(X11E-KL)") (class "Default")
      (node (ref "JP14") (pin "1") (pinfunction "1_1") (pintype "passive"))
      (node (ref "U1") (pin "35") (pinfunction "35_35") (pintype "bidirectional"))
      (node (ref "X11") (pin "5") (pinfunction "KL_5") (pintype "passive"))
    )
    (net (code "92") (name "Net-(X11F-KL)") (class "Default")
      (node (ref "JP12") (pin "1") (pinfunction "1_1") (pintype "passive"))
      (node (ref "U1") (pin "33") (pinfunction "33_33") (pintype "bidirectional"))
      (node (ref "X11") (pin "6") (pinfunction "KL_6") (pintype "passive"))
    )
    (net (code "93") (name "Net-(X12B-KL)") (class "Default")
      (node (ref "JP32") (pin "1") (pinfunction "1_1") (pintype "passive"))
      (node (ref "U1") (pin "53") (pinfunction "53_53") (pintype "bidirectional"))
      (node (ref "X12") (pin "2") (pinfunction "KL_2") (pintype "passive"))
    )
    (net (code "94") (name "Net-(X12C-KL)") (class "Default")
      (node (ref "JP30") (pin "1") (pinfunction "1_1") (pintype "passive"))
      (node (ref "U1") (pin "51") (pinfunction "51_51") (pintype "bidirectional"))
      (node (ref "X12") (pin "3") (pinfunction "KL_3") (pintype "passive"))
    )
    (net (code "95") (name "Net-(X12D-KL)") (class "Default")
      (node (ref "JP28") (pin "1") (pinfunction "1_1") (pintype "passive"))
      (node (ref "U1") (pin "49") (pinfunction "49_49") (pintype "bidirectional"))
      (node (ref "X12") (pin "4") (pinfunction "KL_4") (pintype "passive"))
    )
    (net (code "96") (name "Net-(X12E-KL)") (class "Default")
      (node (ref "JP26") (pin "1") (pinfunction "1_1") (pintype "passive"))
      (node (ref "U1") (pin "47") (pinfunction "47_47") (pintype "bidirectional"))
      (node (ref "X12") (pin "5") (pinfunction "KL_5") (pintype "passive"))
    )
    (net (code "97") (name "Net-(X12F-KL)") (class "Default")
      (node (ref "JP24") (pin "1") (pinfunction "1_1") (pintype "passive"))
      (node (ref "U1") (pin "45") (pinfunction "45_45") (pintype "bidirectional"))
      (node (ref "X12") (pin "6") (pinfunction "KL_6") (pintype "passive"))
    )
    (net (code "98") (name "Net-(X13A-KL)") (class "Default")
      (node (ref "U1") (pin "5V@1") (pinfunction "5V_5V@1") (pintype "bidirectional"))
      (node (ref "X13") (pin "1") (pinfunction "KL_1") (pintype "passive"))
    )
    (net (code "99") (name "Net-(X13B-KL)") (class "Default")
      (node (ref "JP1") (pin "1") (pinfunction "1_1") (pintype "passive"))
      (node (ref "U1") (pin "22") (pinfunction "22_22") (pintype "bidirectional"))
      (node (ref "X13") (pin "2") (pinfunction "KL_2") (pintype "passive"))
    )
    (net (code "100") (name "Net-(X13C-KL)") (class "Default")
      (node (ref "JP3") (pin "1") (pinfunction "1_1") (pintype "passive"))
      (node (ref "U1") (pin "24") (pinfunction "24_24") (pintype "bidirectional"))
      (node (ref "X13") (pin "3") (pinfunction "KL_3") (pintype "passive"))
    )
    (net (code "101") (name "Net-(X13D-KL)") (class "Default")
      (node (ref "JP5") (pin "1") (pinfunction "1_1") (pintype "passive"))
      (node (ref "U1") (pin "26") (pinfunction "26_26") (pintype "bidirectional"))
      (node (ref "X13") (pin "4") (pinfunction "KL_4") (pintype "passive"))
    )
    (net (code "102") (name "Net-(X13E-KL)") (class "Default")
      (node (ref "JP7") (pin "1") (pinfunction "1_1") (pintype "passive"))
      (node (ref "U1") (pin "28") (pinfunction "28_28") (pintype "bidirectional"))
      (node (ref "X13") (pin "5") (pinfunction "KL_5") (pintype "passive"))
    )
    (net (code "103") (name "Net-(X13F-KL)") (class "Default")
      (node (ref "JP9") (pin "1") (pinfunction "1_1") (pintype "passive"))
      (node (ref "U1") (pin "30") (pinfunction "30_30") (pintype "bidirectional"))
      (node (ref "X13") (pin "6") (pinfunction "KL_6") (pintype "passive"))
    )
    (net (code "104") (name "Net-(X14A-KL)") (class "Default")
      (node (ref "JP11") (pin "1") (pinfunction "1_1") (pintype "passive"))
      (node (ref "U1") (pin "32") (pinfunction "32_32") (pintype "bidirectional"))
      (node (ref "X14") (pin "1") (pinfunction "KL_1") (pintype "passive"))
    )
    (net (code "105") (name "Net-(X14B-KL)") (class "Default")
      (node (ref "JP13") (pin "1") (pinfunction "1_1") (pintype "passive"))
      (node (ref "U1") (pin "34") (pinfunction "34_34") (pintype "bidirectional"))
      (node (ref "X14") (pin "2") (pinfunction "KL_2") (pintype "passive"))
    )
    (net (code "106") (name "Net-(X14C-KL)") (class "Default")
      (node (ref "JP15") (pin "1") (pinfunction "1_1") (pintype "passive"))
      (node (ref "U1") (pin "36") (pinfunction "36_36") (pintype "bidirectional"))
      (node (ref "X14") (pin "3") (pinfunction "KL_3") (pintype "passive"))
    )
    (net (code "107") (name "Net-(X14D-KL)") (class "Default")
      (node (ref "JP17") (pin "1") (pinfunction "1_1") (pintype "passive"))
      (node (ref "U1") (pin "38") (pinfunction "38_38") (pintype "bidirectional"))
      (node (ref "X14") (pin "4") (pinfunction "KL_4") (pintype "passive"))
    )
    (net (code "108") (name "Net-(X14E-KL)") (class "Default")
      (node (ref "JP19") (pin "1") (pinfunction "1_1") (pintype "passive"))
      (node (ref "U1") (pin "40") (pinfunction "40_40") (pintype "bidirectional"))
      (node (ref "X14") (pin "5") (pinfunction "KL_5") (pintype "passive"))
    )
    (net (code "109") (name "Net-(X14F-KL)") (class "Default")
      (node (ref "JP21") (pin "1") (pinfunction "1_1") (pintype "passive"))
      (node (ref "U1") (pin "42") (pinfunction "42_42") (pintype "bidirectional"))
      (node (ref "X14") (pin "6") (pinfunction "KL_6") (pintype "passive"))
    )
    (net (code "110") (name "Net-(X15A-KL)") (class "Default")
      (node (ref "JP23") (pin "1") (pinfunction "1_1") (pintype "passive"))
      (node (ref "U1") (pin "44") (pinfunction "44_44") (pintype "bidirectional"))
      (node (ref "X15") (pin "1") (pinfunction "KL_1") (pintype "passive"))
    )
    (net (code "111") (name "Net-(X15B-KL)") (class "Default")
      (node (ref "JP25") (pin "1") (pinfunction "1_1") (pintype "passive"))
      (node (ref "U1") (pin "46") (pinfunction "46_46") (pintype "bidirectional"))
      (node (ref "X15") (pin "2") (pinfunction "KL_2") (pintype "passive"))
    )
    (net (code "112") (name "Net-(X15C-KL)") (class "Default")
      (node (ref "JP27") (pin "1") (pinfunction "1_1") (pintype "passive"))
      (node (ref "U1") (pin "48") (pinfunction "48_48") (pintype "bidirectional"))
      (node (ref "X15") (pin "3") (pinfunction "KL_3") (pintype "passive"))
    )
    (net (code "113") (name "Net-(X15D-KL)") (class "Default")
      (node (ref "JP29") (pin "1") (pinfunction "1_1") (pintype "passive"))
      (node (ref "U1") (pin "50") (pinfunction "50_50") (pintype "bidirectional"))
      (node (ref "X15") (pin "4") (pinfunction "KL_4") (pintype "passive"))
    )
    (net (code "114") (name "Net-(X15E-KL)") (class "Default")
      (node (ref "JP31") (pin "1") (pinfunction "1_1") (pintype "passive"))
      (node (ref "U1") (pin "52") (pinfunction "52_52") (pintype "bidirectional"))
      (node (ref "X15") (pin "5") (pinfunction "KL_5") (pintype "passive"))
    )
    (net (code "115") (name "unconnected-(JP33-Pad1)") (class "Default")
      (node (ref "JP33") (pin "1") (pinfunction "1_1") (pintype "passive"))
    )
    (net (code "116") (name "unconnected-(JP33-Pad2)") (class "Default")
      (node (ref "JP33") (pin "2") (pinfunction "2_2") (pintype "passive"))
    )
    (net (code "117") (name "unconnected-(JP33-Pad3)") (class "Default")
      (node (ref "JP33") (pin "3") (pinfunction "3_3") (pintype "passive"))
    )
    (net (code "118") (name "unconnected-(JP33-Pad4)") (class "Default")
      (node (ref "JP33") (pin "4") (pinfunction "4_4") (pintype "passive"))
    )
    (net (code "119") (name "unconnected-(JP33-Pad5)") (class "Default")
      (node (ref "JP33") (pin "5") (pinfunction "5_5") (pintype "passive"))
    )
    (net (code "120") (name "unconnected-(JP33-Pad6)") (class "Default")
      (node (ref "JP33") (pin "6") (pinfunction "6_6") (pintype "passive"))
    )
    (net (code "121") (name "unconnected-(JP33-Pad7)") (class "Default")
      (node (ref "JP33") (pin "7") (pinfunction "7_7") (pintype "passive"))
    )
    (net (code "122") (name "unconnected-(JP33-Pad8)") (class "Default")
      (node (ref "JP33") (pin "8") (pinfunction "8_8") (pintype "passive"))
    )
    (net (code "123") (name "unconnected-(JP33-Pad9)") (class "Default")
      (node (ref "JP33") (pin "9") (pinfunction "9_9") (pintype "passive"))
    )
    (net (code "124") (name "unconnected-(JP33-Pad10)") (class "Default")
      (node (ref "JP33") (pin "10") (pinfunction "10_10") (pintype "passive"))
    )
    (net (code "125") (name "unconnected-(JP33-Pad11)") (class "Default")
      (node (ref "JP33") (pin "11") (pinfunction "11_11") (pintype "passive"))
    )
    (net (code "126") (name "unconnected-(JP33-Pad12)") (class "Default")
      (node (ref "JP33") (pin "12") (pinfunction "12_12") (pintype "passive"))
    )
    (net (code "127") (name "unconnected-(JP33-Pad13)") (class "Default")
      (node (ref "JP33") (pin "13") (pinfunction "13_13") (pintype "passive"))
    )
    (net (code "128") (name "unconnected-(JP33-Pad14)") (class "Default")
      (node (ref "JP33") (pin "14") (pinfunction "14_14") (pintype "passive"))
    )
    (net (code "129") (name "unconnected-(JP33-Pad15)") (class "Default")
      (node (ref "JP33") (pin "15") (pinfunction "15_15") (pintype "passive"))
    )
    (net (code "130") (name "unconnected-(JP33-Pad16)") (class "Default")
      (node (ref "JP33") (pin "16") (pinfunction "16_16") (pintype "passive"))
    )
    (net (code "131") (name "unconnected-(JP33-Pad17)") (class "Default")
      (node (ref "JP33") (pin "17") (pinfunction "17_17") (pintype "passive"))
    )
    (net (code "132") (name "unconnected-(JP33-Pad18)") (class "Default")
      (node (ref "JP33") (pin "18") (pinfunction "18_18") (pintype "passive"))
    )
    (net (code "133") (name "unconnected-(JP33-Pad19)") (class "Default")
      (node (ref "JP33") (pin "19") (pinfunction "19_19") (pintype "passive"))
    )
    (net (code "134") (name "unconnected-(JP33-Pad20)") (class "Default")
      (node (ref "JP33") (pin "20") (pinfunction "20_20") (pintype "passive"))
    )
    (net (code "135") (name "unconnected-(JP33-Pad21)") (class "Default")
      (node (ref "JP33") (pin "21") (pinfunction "21_21") (pintype "passive"))
    )
    (net (code "136") (name "unconnected-(JP33-Pad22)") (class "Default")
      (node (ref "JP33") (pin "22") (pinfunction "22_22") (pintype "passive"))
    )
    (net (code "137") (name "unconnected-(JP33-Pad23)") (class "Default")
      (node (ref "JP33") (pin "23") (pinfunction "23_23") (pintype "passive"))
    )
    (net (code "138") (name "unconnected-(JP33-Pad24)") (class "Default")
      (node (ref "JP33") (pin "24") (pinfunction "24_24") (pintype "passive"))
    )
    (net (code "139") (name "unconnected-(JP33-Pad25)") (class "Default")
      (node (ref "JP33") (pin "25") (pinfunction "25_25") (pintype "passive"))
    )
    (net (code "140") (name "unconnected-(JP34-Pad1)") (class "Default")
      (node (ref "JP34") (pin "1") (pinfunction "1_1") (pintype "passive"))
    )
    (net (code "141") (name "unconnected-(JP34-Pad2)") (class "Default")
      (node (ref "JP34") (pin "2") (pinfunction "2_2") (pintype "passive"))
    )
    (net (code "142") (name "unconnected-(JP34-Pad3)") (class "Default")
      (node (ref "JP34") (pin "3") (pinfunction "3_3") (pintype "passive"))
    )
    (net (code "143") (name "unconnected-(JP34-Pad4)") (class "Default")
      (node (ref "JP34") (pin "4") (pinfunction "4_4") (pintype "passive"))
    )
    (net (code "144") (name "unconnected-(JP34-Pad5)") (class "Default")
      (node (ref "JP34") (pin "5") (pinfunction "5_5") (pintype "passive"))
    )
    (net (code "145") (name "unconnected-(JP34-Pad6)") (class "Default")
      (node (ref "JP34") (pin "6") (pinfunction "6_6") (pintype "passive"))
    )
    (net (code "146") (name "unconnected-(JP34-Pad7)") (class "Default")
      (node (ref "JP34") (pin "7") (pinfunction "7_7") (pintype "passive"))
    )
    (net (code "147") (name "unconnected-(JP34-Pad8)") (class "Default")
      (node (ref "JP34") (pin "8") (pinfunction "8_8") (pintype "passive"))
    )
    (net (code "148") (name "unconnected-(JP34-Pad9)") (class "Default")
      (node (ref "JP34") (pin "9") (pinfunction "9_9") (pintype "passive"))
    )
    (net (code "149") (name "unconnected-(JP34-Pad10)") (class "Default")
      (node (ref "JP34") (pin "10") (pinfunction "10_10") (pintype "passive"))
    )
    (net (code "150") (name "unconnected-(JP34-Pad11)") (class "Default")
      (node (ref "JP34") (pin "11") (pinfunction "11_11") (pintype "passive"))
    )
    (net (code "151") (name "unconnected-(JP34-Pad12)") (class "Default")
      (node (ref "JP34") (pin "12") (pinfunction "12_12") (pintype "passive"))
    )
    (net (code "152") (name "unconnected-(JP34-Pad13)") (class "Default")
      (node (ref "JP34") (pin "13") (pinfunction "13_13") (pintype "passive"))
    )
    (net (code "153") (name "unconnected-(JP34-Pad14)") (class "Default")
      (node (ref "JP34") (pin "14") (pinfunction "14_14") (pintype "passive"))
    )
    (net (code "154") (name "unconnected-(JP34-Pad15)") (class "Default")
      (node (ref "JP34") (pin "15") (pinfunction "15_15") (pintype "passive"))
    )
    (net (code "155") (name "unconnected-(JP34-Pad16)") (class "Default")
      (node (ref "JP34") (pin "16") (pinfunction "16_16") (pintype "passive"))
    )
    (net (code "156") (name "unconnected-(JP34-Pad17)") (class "Default")
      (node (ref "JP34") (pin "17") (pinfunction "17_17") (pintype "passive"))
    )
    (net (code "157") (name "unconnected-(JP34-Pad18)") (class "Default")
      (node (ref "JP34") (pin "18") (pinfunction "18_18") (pintype "passive"))
    )
    (net (code "158") (name "unconnected-(JP34-Pad19)") (class "Default")
      (node (ref "JP34") (pin "19") (pinfunction "19_19") (pintype "passive"))
    )
    (net (code "159") (name "unconnected-(JP34-Pad20)") (class "Default")
      (node (ref "JP34") (pin "20") (pinfunction "20_20") (pintype "passive"))
    )
    (net (code "160") (name "unconnected-(JP34-Pad21)") (class "Default")
      (node (ref "JP34") (pin "21") (pinfunction "21_21") (pintype "passive"))
    )
    (net (code "161") (name "unconnected-(JP34-Pad22)") (class "Default")
      (node (ref "JP34") (pin "22") (pinfunction "22_22") (pintype "passive"))
    )
    (net (code "162") (name "unconnected-(JP34-Pad23)") (class "Default")
      (node (ref "JP34") (pin "23") (pinfunction "23_23") (pintype "passive"))
    )
    (net (code "163") (name "unconnected-(JP34-Pad24)") (class "Default")
      (node (ref "JP34") (pin "24") (pinfunction "24_24") (pintype "passive"))
    )
    (net (code "164") (name "unconnected-(JP34-Pad25)") (class "Default")
      (node (ref "JP34") (pin "25") (pinfunction "25_25") (pintype "passive"))
    )
    (net (code "165") (name "unconnected-(JP35-Pad1)") (class "Default")
      (node (ref "JP35") (pin "1") (pinfunction "1_1") (pintype "passive"))
    )
    (net (code "166") (name "unconnected-(JP35-Pad2)") (class "Default")
      (node (ref "JP35") (pin "2") (pinfunction "2_2") (pintype "passive"))
    )
    (net (code "167") (name "unconnected-(JP35-Pad3)") (class "Default")
      (node (ref "JP35") (pin "3") (pinfunction "3_3") (pintype "passive"))
    )
    (net (code "168") (name "unconnected-(JP35-Pad4)") (class "Default")
      (node (ref "JP35") (pin "4") (pinfunction "4_4") (pintype "passive"))
    )
    (net (code "169") (name "unconnected-(JP35-Pad5)") (class "Default")
      (node (ref "JP35") (pin "5") (pinfunction "5_5") (pintype "passive"))
    )
    (net (code "170") (name "unconnected-(JP35-Pad6)") (class "Default")
      (node (ref "JP35") (pin "6") (pinfunction "6_6") (pintype "passive"))
    )
    (net (code "171") (name "unconnected-(JP35-Pad7)") (class "Default")
      (node (ref "JP35") (pin "7") (pinfunction "7_7") (pintype "passive"))
    )
    (net (code "172") (name "unconnected-(JP35-Pad8)") (class "Default")
      (node (ref "JP35") (pin "8") (pinfunction "8_8") (pintype "passive"))
    )
    (net (code "173") (name "unconnected-(JP35-Pad9)") (class "Default")
      (node (ref "JP35") (pin "9") (pinfunction "9_9") (pintype "passive"))
    )
    (net (code "174") (name "unconnected-(JP35-Pad10)") (class "Default")
      (node (ref "JP35") (pin "10") (pinfunction "10_10") (pintype "passive"))
    )
    (net (code "175") (name "unconnected-(JP35-Pad11)") (class "Default")
      (node (ref "JP35") (pin "11") (pinfunction "11_11") (pintype "passive"))
    )
    (net (code "176") (name "unconnected-(JP35-Pad12)") (class "Default")
      (node (ref "JP35") (pin "12") (pinfunction "12_12") (pintype "passive"))
    )
    (net (code "177") (name "unconnected-(JP35-Pad13)") (class "Default")
      (node (ref "JP35") (pin "13") (pinfunction "13_13") (pintype "passive"))
    )
    (net (code "178") (name "unconnected-(JP35-Pad14)") (class "Default")
      (node (ref "JP35") (pin "14") (pinfunction "14_14") (pintype "passive"))
    )
    (net (code "179") (name "unconnected-(JP35-Pad15)") (class "Default")
      (node (ref "JP35") (pin "15") (pinfunction "15_15") (pintype "passive"))
    )
    (net (code "180") (name "unconnected-(JP35-Pad16)") (class "Default")
      (node (ref "JP35") (pin "16") (pinfunction "16_16") (pintype "passive"))
    )
    (net (code "181") (name "unconnected-(JP35-Pad17)") (class "Default")
      (node (ref "JP35") (pin "17") (pinfunction "17_17") (pintype "passive"))
    )
    (net (code "182") (name "unconnected-(JP35-Pad18)") (class "Default")
      (node (ref "JP35") (pin "18") (pinfunction "18_18") (pintype "passive"))
    )
    (net (code "183") (name "unconnected-(JP35-Pad19)") (class "Default")
      (node (ref "JP35") (pin "19") (pinfunction "19_19") (pintype "passive"))
    )
    (net (code "184") (name "unconnected-(JP35-Pad20)") (class "Default")
      (node (ref "JP35") (pin "20") (pinfunction "20_20") (pintype "passive"))
    )
    (net (code "185") (name "unconnected-(JP35-Pad21)") (class "Default")
      (node (ref "JP35") (pin "21") (pinfunction "21_21") (pintype "passive"))
    )
    (net (code "186") (name "unconnected-(JP35-Pad22)") (class "Default")
      (node (ref "JP35") (pin "22") (pinfunction "22_22") (pintype "passive"))
    )
    (net (code "187") (name "unconnected-(JP35-Pad23)") (class "Default")
      (node (ref "JP35") (pin "23") (pinfunction "23_23") (pintype "passive"))
    )
    (net (code "188") (name "unconnected-(JP35-Pad24)") (class "Default")
      (node (ref "JP35") (pin "24") (pinfunction "24_24") (pintype "passive"))
    )
    (net (code "189") (name "unconnected-(JP35-Pad25)") (class "Default")
      (node (ref "JP35") (pin "25") (pinfunction "25_25") (pintype "passive"))
    )
    (net (code "190") (name "unconnected-(JP37-Pad1)") (class "Default")
      (node (ref "JP37") (pin "1") (pinfunction "1_1") (pintype "passive"))
    )
    (net (code "191") (name "unconnected-(JP37-Pad2)") (class "Default")
      (node (ref "JP37") (pin "2") (pinfunction "2_2") (pintype "passive"))
    )
    (net (code "192") (name "unconnected-(JP37-Pad3)") (class "Default")
      (node (ref "JP37") (pin "3") (pinfunction "3_3") (pintype "passive"))
    )
    (net (code "193") (name "unconnected-(JP37-Pad4)") (class "Default")
      (node (ref "JP37") (pin "4") (pinfunction "4_4") (pintype "passive"))
    )
    (net (code "194") (name "unconnected-(JP37-Pad5)") (class "Default")
      (node (ref "JP37") (pin "5") (pinfunction "5_5") (pintype "passive"))
    )
    (net (code "195") (name "unconnected-(JP37-Pad6)") (class "Default")
      (node (ref "JP37") (pin "6") (pinfunction "6_6") (pintype "passive"))
    )
    (net (code "196") (name "unconnected-(JP37-Pad7)") (class "Default")
      (node (ref "JP37") (pin "7") (pinfunction "7_7") (pintype "passive"))
    )
    (net (code "197") (name "unconnected-(JP37-Pad8)") (class "Default")
      (node (ref "JP37") (pin "8") (pinfunction "8_8") (pintype "passive"))
    )
    (net (code "198") (name "unconnected-(JP37-Pad9)") (class "Default")
      (node (ref "JP37") (pin "9") (pinfunction "9_9") (pintype "passive"))
    )
    (net (code "199") (name "unconnected-(JP37-Pad10)") (class "Default")
      (node (ref "JP37") (pin "10") (pinfunction "10_10") (pintype "passive"))
    )
    (net (code "200") (name "unconnected-(JP37-Pad11)") (class "Default")
      (node (ref "JP37") (pin "11") (pinfunction "11_11") (pintype "passive"))
    )
    (net (code "201") (name "unconnected-(JP37-Pad12)") (class "Default")
      (node (ref "JP37") (pin "12") (pinfunction "12_12") (pintype "passive"))
    )
    (net (code "202") (name "unconnected-(JP37-Pad13)") (class "Default")
      (node (ref "JP37") (pin "13") (pinfunction "13_13") (pintype "passive"))
    )
    (net (code "203") (name "unconnected-(JP37-Pad14)") (class "Default")
      (node (ref "JP37") (pin "14") (pinfunction "14_14") (pintype "passive"))
    )
    (net (code "204") (name "unconnected-(JP37-Pad15)") (class "Default")
      (node (ref "JP37") (pin "15") (pinfunction "15_15") (pintype "passive"))
    )
    (net (code "205") (name "unconnected-(JP37-Pad16)") (class "Default")
      (node (ref "JP37") (pin "16") (pinfunction "16_16") (pintype "passive"))
    )
    (net (code "206") (name "unconnected-(JP38-Pad1)") (class "Default")
      (node (ref "JP38") (pin "1") (pinfunction "1_1") (pintype "passive"))
    )
    (net (code "207") (name "unconnected-(JP38-Pad2)") (class "Default")
      (node (ref "JP38") (pin "2") (pinfunction "2_2") (pintype "passive"))
    )
    (net (code "208") (name "unconnected-(JP38-Pad3)") (class "Default")
      (node (ref "JP38") (pin "3") (pinfunction "3_3") (pintype "passive"))
    )
    (net (code "209") (name "unconnected-(JP38-Pad4)") (class "Default")
      (node (ref "JP38") (pin "4") (pinfunction "4_4") (pintype "passive"))
    )
    (net (code "210") (name "unconnected-(JP38-Pad5)") (class "Default")
      (node (ref "JP38") (pin "5") (pinfunction "5_5") (pintype "passive"))
    )
    (net (code "211") (name "unconnected-(JP38-Pad6)") (class "Default")
      (node (ref "JP38") (pin "6") (pinfunction "6_6") (pintype "passive"))
    )
    (net (code "212") (name "unconnected-(JP38-Pad7)") (class "Default")
      (node (ref "JP38") (pin "7") (pinfunction "7_7") (pintype "passive"))
    )
    (net (code "213") (name "unconnected-(JP38-Pad8)") (class "Default")
      (node (ref "JP38") (pin "8") (pinfunction "8_8") (pintype "passive"))
    )
    (net (code "214") (name "unconnected-(JP38-Pad9)") (class "Default")
      (node (ref "JP38") (pin "9") (pinfunction "9_9") (pintype "passive"))
    )
    (net (code "215") (name "unconnected-(JP38-Pad10)") (class "Default")
      (node (ref "JP38") (pin "10") (pinfunction "10_10") (pintype "passive"))
    )
    (net (code "216") (name "unconnected-(JP38-Pad11)") (class "Default")
      (node (ref "JP38") (pin "11") (pinfunction "11_11") (pintype "passive"))
    )
    (net (code "217") (name "unconnected-(JP38-Pad12)") (class "Default")
      (node (ref "JP38") (pin "12") (pinfunction "12_12") (pintype "passive"))
    )
    (net (code "218") (name "unconnected-(JP38-Pad13)") (class "Default")
      (node (ref "JP38") (pin "13") (pinfunction "13_13") (pintype "passive"))
    )
    (net (code "219") (name "unconnected-(JP38-Pad14)") (class "Default")
      (node (ref "JP38") (pin "14") (pinfunction "14_14") (pintype "passive"))
    )
    (net (code "220") (name "unconnected-(JP38-Pad15)") (class "Default")
      (node (ref "JP38") (pin "15") (pinfunction "15_15") (pintype "passive"))
    )
    (net (code "221") (name "unconnected-(JP38-Pad16)") (class "Default")
      (node (ref "JP38") (pin "16") (pinfunction "16_16") (pintype "passive"))
    )
    (net (code "222") (name "unconnected-(JP39-Pad1)") (class "Default")
      (node (ref "JP39") (pin "1") (pinfunction "1_1") (pintype "passive"))
    )
    (net (code "223") (name "unconnected-(JP39-Pad2)") (class "Default")
      (node (ref "JP39") (pin "2") (pinfunction "2_2") (pintype "passive"))
    )
    (net (code "224") (name "unconnected-(JP39-Pad3)") (class "Default")
      (node (ref "JP39") (pin "3") (pinfunction "3_3") (pintype "passive"))
    )
    (net (code "225") (name "unconnected-(JP39-Pad4)") (class "Default")
      (node (ref "JP39") (pin "4") (pinfunction "4_4") (pintype "passive"))
    )
    (net (code "226") (name "unconnected-(JP39-Pad5)") (class "Default")
      (node (ref "JP39") (pin "5") (pinfunction "5_5") (pintype "passive"))
    )
    (net (code "227") (name "unconnected-(JP39-Pad6)") (class "Default")
      (node (ref "JP39") (pin "6") (pinfunction "6_6") (pintype "passive"))
    )
    (net (code "228") (name "unconnected-(JP39-Pad7)") (class "Default")
      (node (ref "JP39") (pin "7") (pinfunction "7_7") (pintype "passive"))
    )
    (net (code "229") (name "unconnected-(JP39-Pad8)") (class "Default")
      (node (ref "JP39") (pin "8") (pinfunction "8_8") (pintype "passive"))
    )
    (net (code "230") (name "unconnected-(JP39-Pad9)") (class "Default")
      (node (ref "JP39") (pin "9") (pinfunction "9_9") (pintype "passive"))
    )
    (net (code "231") (name "unconnected-(JP39-Pad10)") (class "Default")
      (node (ref "JP39") (pin "10") (pinfunction "10_10") (pintype "passive"))
    )
    (net (code "232") (name "unconnected-(JP39-Pad11)") (class "Default")
      (node (ref "JP39") (pin "11") (pinfunction "11_11") (pintype "passive"))
    )
    (net (code "233") (name "unconnected-(JP39-Pad12)") (class "Default")
      (node (ref "JP39") (pin "12") (pinfunction "12_12") (pintype "passive"))
    )
    (net (code "234") (name "unconnected-(JP39-Pad13)") (class "Default")
      (node (ref "JP39") (pin "13") (pinfunction "13_13") (pintype "passive"))
    )
    (net (code "235") (name "unconnected-(JP39-Pad14)") (class "Default")
      (node (ref "JP39") (pin "14") (pinfunction "14_14") (pintype "passive"))
    )
    (net (code "236") (name "unconnected-(JP39-Pad15)") (class "Default")
      (node (ref "JP39") (pin "15") (pinfunction "15_15") (pintype "passive"))
    )
    (net (code "237") (name "unconnected-(JP39-Pad16)") (class "Default")
      (node (ref "JP39") (pin "16") (pinfunction "16_16") (pintype "passive"))
    )
    (net (code "238") (name "unconnected-(JP40-Pad1)") (class "Default")
      (node (ref "JP40") (pin "1") (pinfunction "1_1") (pintype "passive"))
    )
    (net (code "239") (name "unconnected-(JP40-Pad2)") (class "Default")
      (node (ref "JP40") (pin "2") (pinfunction "2_2") (pintype "passive"))
    )
    (net (code "240") (name "unconnected-(JP40-Pad3)") (class "Default")
      (node (ref "JP40") (pin "3") (pinfunction "3_3") (pintype "passive"))
    )
    (net (code "241") (name "unconnected-(JP40-Pad4)") (class "Default")
      (node (ref "JP40") (pin "4") (pinfunction "4_4") (pintype "passive"))
    )
    (net (code "242") (name "unconnected-(JP40-Pad5)") (class "Default")
      (node (ref "JP40") (pin "5") (pinfunction "5_5") (pintype "passive"))
    )
    (net (code "243") (name "unconnected-(JP40-Pad6)") (class "Default")
      (node (ref "JP40") (pin "6") (pinfunction "6_6") (pintype "passive"))
    )
    (net (code "244") (name "unconnected-(JP40-Pad7)") (class "Default")
      (node (ref "JP40") (pin "7") (pinfunction "7_7") (pintype "passive"))
    )
    (net (code "245") (name "unconnected-(JP40-Pad8)") (class "Default")
      (node (ref "JP40") (pin "8") (pinfunction "8_8") (pintype "passive"))
    )
    (net (code "246") (name "unconnected-(JP40-Pad9)") (class "Default")
      (node (ref "JP40") (pin "9") (pinfunction "9_9") (pintype "passive"))
    )
    (net (code "247") (name "unconnected-(JP40-Pad10)") (class "Default")
      (node (ref "JP40") (pin "10") (pinfunction "10_10") (pintype "passive"))
    )
    (net (code "248") (name "unconnected-(JP40-Pad11)") (class "Default")
      (node (ref "JP40") (pin "11") (pinfunction "11_11") (pintype "passive"))
    )
    (net (code "249") (name "unconnected-(JP40-Pad12)") (class "Default")
      (node (ref "JP40") (pin "12") (pinfunction "12_12") (pintype "passive"))
    )
    (net (code "250") (name "unconnected-(JP40-Pad13)") (class "Default")
      (node (ref "JP40") (pin "13") (pinfunction "13_13") (pintype "passive"))
    )
    (net (code "251") (name "unconnected-(JP40-Pad14)") (class "Default")
      (node (ref "JP40") (pin "14") (pinfunction "14_14") (pintype "passive"))
    )
    (net (code "252") (name "unconnected-(JP40-Pad15)") (class "Default")
      (node (ref "JP40") (pin "15") (pinfunction "15_15") (pintype "passive"))
    )
    (net (code "253") (name "unconnected-(JP40-Pad16)") (class "Default")
      (node (ref "JP40") (pin "16") (pinfunction "16_16") (pintype "passive"))
    )
    (net (code "254") (name "unconnected-(JP41-Pad1)") (class "Default")
      (node (ref "JP41") (pin "1") (pinfunction "1_1") (pintype "passive"))
    )
    (net (code "255") (name "unconnected-(JP41-Pad2)") (class "Default")
      (node (ref "JP41") (pin "2") (pinfunction "2_2") (pintype "passive"))
    )
    (net (code "256") (name "unconnected-(JP41-Pad3)") (class "Default")
      (node (ref "JP41") (pin "3") (pinfunction "3_3") (pintype "passive"))
    )
    (net (code "257") (name "unconnected-(JP41-Pad4)") (class "Default")
      (node (ref "JP41") (pin "4") (pinfunction "4_4") (pintype "passive"))
    )
    (net (code "258") (name "unconnected-(JP41-Pad5)") (class "Default")
      (node (ref "JP41") (pin "5") (pinfunction "5_5") (pintype "passive"))
    )
    (net (code "259") (name "unconnected-(JP41-Pad6)") (class "Default")
      (node (ref "JP41") (pin "6") (pinfunction "6_6") (pintype "passive"))
    )
    (net (code "260") (name "unconnected-(JP41-Pad7)") (class "Default")
      (node (ref "JP41") (pin "7") (pinfunction "7_7") (pintype "passive"))
    )
    (net (code "261") (name "unconnected-(JP41-Pad8)") (class "Default")
      (node (ref "JP41") (pin "8") (pinfunction "8_8") (pintype "passive"))
    )
    (net (code "262") (name "unconnected-(JP41-Pad9)") (class "Default")
      (node (ref "JP41") (pin "9") (pinfunction "9_9") (pintype "passive"))
    )
    (net (code "263") (name "unconnected-(JP41-Pad10)") (class "Default")
      (node (ref "JP41") (pin "10") (pinfunction "10_10") (pintype "passive"))
    )
    (net (code "264") (name "unconnected-(JP41-Pad11)") (class "Default")
      (node (ref "JP41") (pin "11") (pinfunction "11_11") (pintype "passive"))
    )
    (net (code "265") (name "unconnected-(JP41-Pad12)") (class "Default")
      (node (ref "JP41") (pin "12") (pinfunction "12_12") (pintype "passive"))
    )
    (net (code "266") (name "unconnected-(JP41-Pad13)") (class "Default")
      (node (ref "JP41") (pin "13") (pinfunction "13_13") (pintype "passive"))
    )
    (net (code "267") (name "unconnected-(JP41-Pad14)") (class "Default")
      (node (ref "JP41") (pin "14") (pinfunction "14_14") (pintype "passive"))
    )
    (net (code "268") (name "unconnected-(JP41-Pad15)") (class "Default")
      (node (ref "JP41") (pin "15") (pinfunction "15_15") (pintype "passive"))
    )
    (net (code "269") (name "unconnected-(JP41-Pad16)") (class "Default")
      (node (ref "JP41") (pin "16") (pinfunction "16_16") (pintype "passive"))
    )
  )
)
